# Sampling.net
KiCad netlist of a schematic drawn in Altium Designer
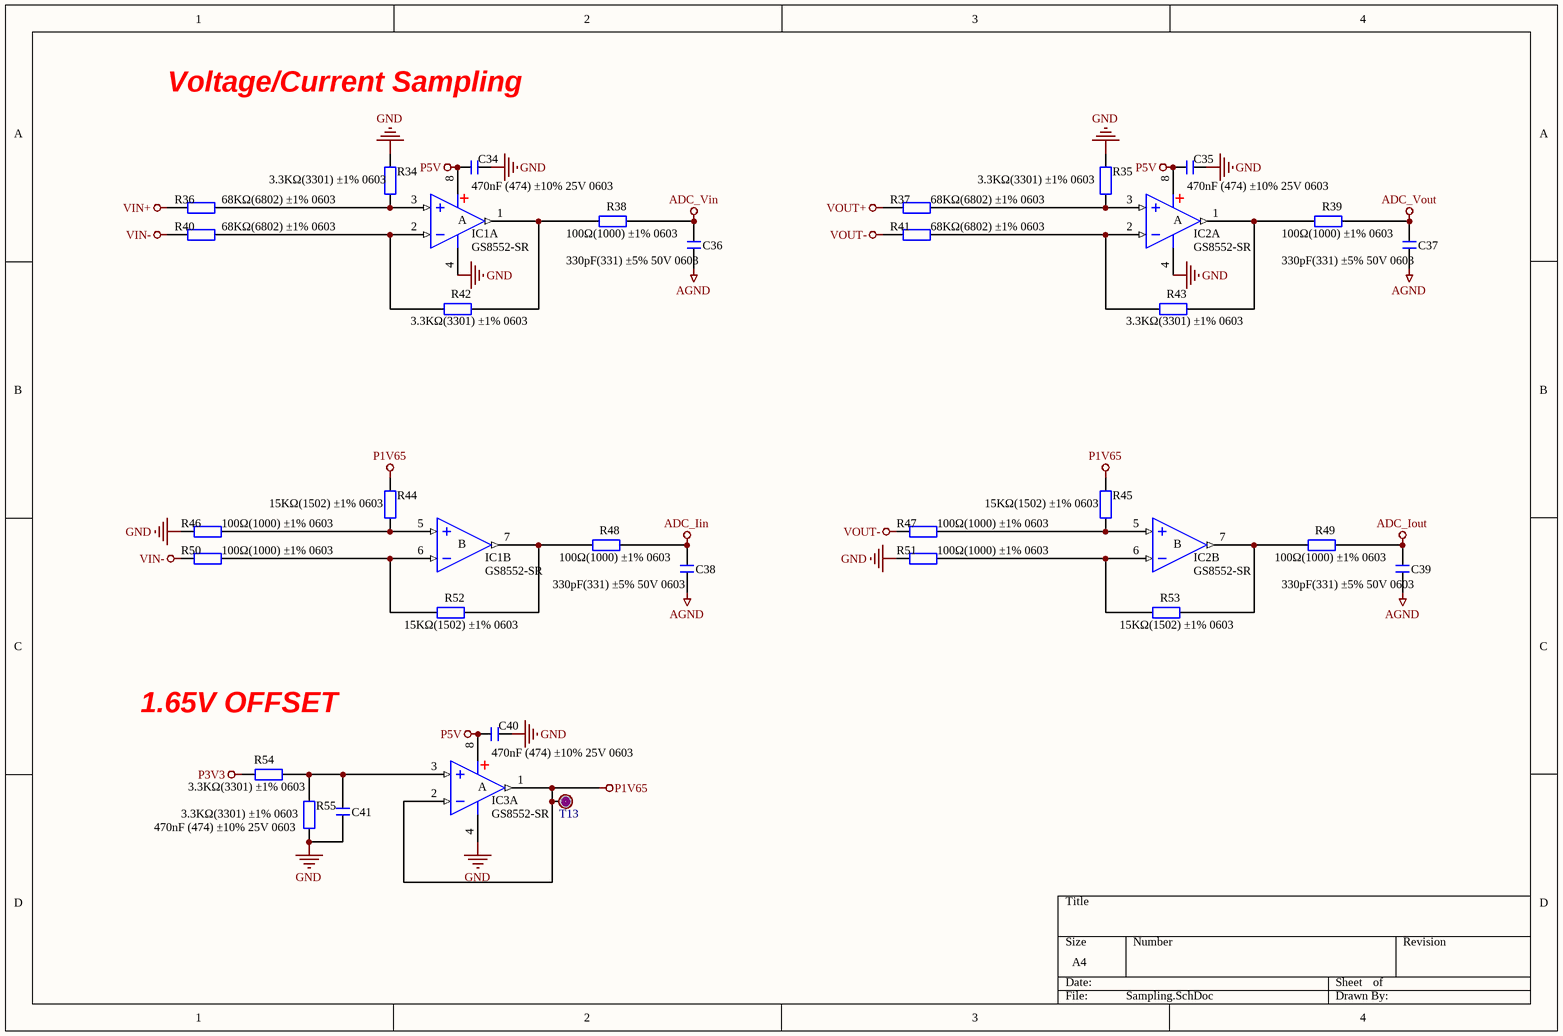
[diagram p0: Sampling.SchDoc]

(export (version "E")
  (design (tool "Eeschema 10.0.6"))
  (components
    (comp (ref "C34")
      (value "470nF (474) ±10% 25V 0603")
      (footprint "C 0603_L")
      (description "贴片电容")
      (libsource (lib "0.1 - 电阻-电容-电感") (part "C"))
    )
    (comp (ref "C35")
      (value "470nF (474) ±10% 25V 0603")
      (footprint "C 0603_L")
      (description "贴片电容")
      (libsource (lib "0.1 - 电阻-电容-电感") (part "C"))
    )
    (comp (ref "C36")
      (value "330pF(331) ±5% 50V 0603")
      (footprint "C 0603_L")
      (description "贴片电容")
      (libsource (lib "0.1 - 电阻-电容-电感") (part "C"))
    )
    (comp (ref "C37")
      (value "330pF(331) ±5% 50V 0603")
      (footprint "C 0603_L")
      (description "贴片电容")
      (libsource (lib "0.1 - 电阻-电容-电感") (part "C"))
    )
    (comp (ref "C38")
      (value "330pF(331) ±5% 50V 0603")
      (footprint "C 0603_L")
      (description "贴片电容")
      (libsource (lib "0.1 - 电阻-电容-电感") (part "C"))
    )
    (comp (ref "C39")
      (value "330pF(331) ±5% 50V 0603")
      (footprint "C 0603_L")
      (description "贴片电容")
      (libsource (lib "0.1 - 电阻-电容-电感") (part "C"))
    )
    (comp (ref "C40")
      (value "470nF (474) ±10% 25V 0603")
      (footprint "C 0603_L")
      (description "贴片电容")
      (libsource (lib "0.1 - 电阻-电容-电感") (part "C"))
    )
    (comp (ref "C41")
      (value "470nF (474) ±10% 25V 0603")
      (footprint "C 0603_L")
      (description "贴片电容")
      (libsource (lib "0.1 - 电阻-电容-电感") (part "C"))
    )
    (comp (ref "IC1")
      (value "GS8552-SR")
      (footprint "SOP8_N")
      (description "双路运放")
      (fields (field (name "版权归属") "源创客"))
      (libsource (lib "1.0 - 常见芯片") (part "LM358"))
    )
    (comp (ref "IC2")
      (value "GS8552-SR")
      (footprint "SOP8_N")
      (description "双路运放")
      (fields (field (name "版权归属") "源创客"))
      (libsource (lib "1.0 - 常见芯片") (part "LM358"))
    )
    (comp (ref "IC3")
      (value "GS8552-SR")
      (footprint "SOP8_N")
      (description "双路运放")
      (fields (field (name "版权归属") "源创客"))
      (libsource (lib "1.0 - 常见芯片") (part "LM358"))
    )
    (comp (ref "R34")
      (value "3.3KΩ(3301) ±1% 0603")
      (footprint "R 0603_L")
      (description "贴片电阻")
      (fields (field (name "版权归属") "来自淘宝 ID：黄晶宝石"))
      (libsource (lib "0.1 - 电阻-电容-电感") (part "R"))
    )
    (comp (ref "R35")
      (value "3.3KΩ(3301) ±1% 0603")
      (footprint "R 0603_L")
      (description "贴片电阻")
      (fields (field (name "版权归属") "来自淘宝 ID：黄晶宝石"))
      (libsource (lib "0.1 - 电阻-电容-电感") (part "R"))
    )
    (comp (ref "R36")
      (value "68KΩ(6802) ±1% 0603")
      (footprint "R 0603_L")
      (description "贴片电阻")
      (fields (field (name "版权归属") "来自淘宝 ID：黄晶宝石"))
      (libsource (lib "0.1 - 电阻-电容-电感") (part "R"))
    )
    (comp (ref "R37")
      (value "68KΩ(6802) ±1% 0603")
      (footprint "R 0603_L")
      (description "贴片电阻")
      (fields (field (name "版权归属") "来自淘宝 ID：黄晶宝石"))
      (libsource (lib "0.1 - 电阻-电容-电感") (part "R"))
    )
    (comp (ref "R38")
      (value "100Ω(1000) ±1% 0603")
      (footprint "R 0603_L")
      (description "贴片电阻")
      (fields (field (name "版权归属") "来自淘宝 ID：黄晶宝石"))
      (libsource (lib "0.1 - 电阻-电容-电感") (part "R"))
    )
    (comp (ref "R39")
      (value "100Ω(1000) ±1% 0603")
      (footprint "R 0603_L")
      (description "贴片电阻")
      (fields (field (name "版权归属") "来自淘宝 ID：黄晶宝石"))
      (libsource (lib "0.1 - 电阻-电容-电感") (part "R"))
    )
    (comp (ref "R40")
      (value "68KΩ(6802) ±1% 0603")
      (footprint "R 0603_L")
      (description "贴片电阻")
      (fields (field (name "版权归属") "来自淘宝 ID：黄晶宝石"))
      (libsource (lib "0.1 - 电阻-电容-电感") (part "R"))
    )
    (comp (ref "R41")
      (value "68KΩ(6802) ±1% 0603")
      (footprint "R 0603_L")
      (description "贴片电阻")
      (fields (field (name "版权归属") "来自淘宝 ID：黄晶宝石"))
      (libsource (lib "0.1 - 电阻-电容-电感") (part "R"))
    )
    (comp (ref "R42")
      (value "3.3KΩ(3301) ±1% 0603")
      (footprint "R 0603_L")
      (description "贴片电阻")
      (fields (field (name "版权归属") "来自淘宝 ID：黄晶宝石"))
      (libsource (lib "0.1 - 电阻-电容-电感") (part "R"))
    )
    (comp (ref "R43")
      (value "3.3KΩ(3301) ±1% 0603")
      (footprint "R 0603_L")
      (description "贴片电阻")
      (fields (field (name "版权归属") "来自淘宝 ID：黄晶宝石"))
      (libsource (lib "0.1 - 电阻-电容-电感") (part "R"))
    )
    (comp (ref "R44")
      (value "15KΩ(1502) ±1% 0603")
      (footprint "R 0603_L")
      (description "贴片电阻")
      (fields (field (name "版权归属") "来自淘宝 ID：黄晶宝石"))
      (libsource (lib "0.1 - 电阻-电容-电感") (part "R"))
    )
    (comp (ref "R45")
      (value "15KΩ(1502) ±1% 0603")
      (footprint "R 0603_L")
      (description "贴片电阻")
      (fields (field (name "版权归属") "来自淘宝 ID：黄晶宝石"))
      (libsource (lib "0.1 - 电阻-电容-电感") (part "R"))
    )
    (comp (ref "R46")
      (value "100Ω(1000) ±1% 0603")
      (footprint "R 0603_L")
      (description "贴片电阻")
      (fields (field (name "版权归属") "来自淘宝 ID：黄晶宝石"))
      (libsource (lib "0.1 - 电阻-电容-电感") (part "R"))
    )
    (comp (ref "R47")
      (value "100Ω(1000) ±1% 0603")
      (footprint "R 0603_L")
      (description "贴片电阻")
      (fields (field (name "版权归属") "来自淘宝 ID：黄晶宝石"))
      (libsource (lib "0.1 - 电阻-电容-电感") (part "R"))
    )
    (comp (ref "R48")
      (value "100Ω(1000) ±1% 0603")
      (footprint "R 0603_L")
      (description "贴片电阻")
      (fields (field (name "版权归属") "来自淘宝 ID：黄晶宝石"))
      (libsource (lib "0.1 - 电阻-电容-电感") (part "R"))
    )
    (comp (ref "R49")
      (value "100Ω(1000) ±1% 0603")
      (footprint "R 0603_L")
      (description "贴片电阻")
      (fields (field (name "版权归属") "来自淘宝 ID：黄晶宝石"))
      (libsource (lib "0.1 - 电阻-电容-电感") (part "R"))
    )
    (comp (ref "R50")
      (value "100Ω(1000) ±1% 0603")
      (footprint "R 0603_L")
      (description "贴片电阻")
      (fields (field (name "版权归属") "来自淘宝 ID：黄晶宝石"))
      (libsource (lib "0.1 - 电阻-电容-电感") (part "R"))
    )
    (comp (ref "R51")
      (value "100Ω(1000) ±1% 0603")
      (footprint "R 0603_L")
      (description "贴片电阻")
      (fields (field (name "版权归属") "来自淘宝 ID：黄晶宝石"))
      (libsource (lib "0.1 - 电阻-电容-电感") (part "R"))
    )
    (comp (ref "R52")
      (value "15KΩ(1502) ±1% 0603")
      (footprint "R 0603_L")
      (description "贴片电阻")
      (fields (field (name "版权归属") "来自淘宝 ID：黄晶宝石"))
      (libsource (lib "0.1 - 电阻-电容-电感") (part "R"))
    )
    (comp (ref "R53")
      (value "15KΩ(1502) ±1% 0603")
      (footprint "R 0603_L")
      (description "贴片电阻")
      (fields (field (name "版权归属") "来自淘宝 ID：黄晶宝石"))
      (libsource (lib "0.1 - 电阻-电容-电感") (part "R"))
    )
    (comp (ref "R54")
      (value "3.3KΩ(3301) ±1% 0603")
      (footprint "R 0603_L")
      (description "贴片电阻")
      (fields (field (name "版权归属") "来自淘宝 ID：黄晶宝石"))
      (libsource (lib "0.1 - 电阻-电容-电感") (part "R"))
    )
    (comp (ref "R55")
      (value "3.3KΩ(3301) ±1% 0603")
      (footprint "R 0603_L")
      (description "贴片电阻")
      (fields (field (name "版权归属") "来自淘宝 ID：黄晶宝石"))
      (libsource (lib "0.1 - 电阻-电容-电感") (part "R"))
    )
    (comp (ref "T13") (value "TestP") (footprint "TestP") (libsource (lib "CSS02404A") (part "TestP")))
  )
  (nets
    (net (code "1") (name "ADC_Iin") (class "Default")
      (node (ref "C38") (pin "2") (pinfunction "2_2") (pintype "passive"))
      (node (ref "R48") (pin "2") (pinfunction "2_2") (pintype "passive"))
    )
    (net (code "2") (name "ADC_Iout") (class "Default")
      (node (ref "C39") (pin "2") (pinfunction "2_2") (pintype "passive"))
      (node (ref "R49") (pin "2") (pinfunction "2_2") (pintype "passive"))
    )
    (net (code "3") (name "ADC_Vin") (class "Default")
      (node (ref "C36") (pin "2") (pinfunction "2_2") (pintype "passive"))
      (node (ref "R38") (pin "2") (pinfunction "2_2") (pintype "passive"))
    )
    (net (code "4") (name "ADC_Vout") (class "Default")
      (node (ref "C37") (pin "2") (pinfunction "2_2") (pintype "passive"))
      (node (ref "R39") (pin "2") (pinfunction "2_2") (pintype "passive"))
    )
    (net (code "5") (name "AGND") (class "Default")
      (node (ref "C36") (pin "1") (pinfunction "1_1") (pintype "passive"))
      (node (ref "C37") (pin "1") (pinfunction "1_1") (pintype "passive"))
      (node (ref "C38") (pin "1") (pinfunction "1_1") (pintype "passive"))
      (node (ref "C39") (pin "1") (pinfunction "1_1") (pintype "passive"))
    )
    (net (code "6") (name "GND") (class "Default")
      (node (ref "C34") (pin "1") (pinfunction "1_1") (pintype "passive"))
      (node (ref "C35") (pin "1") (pinfunction "1_1") (pintype "passive"))
      (node (ref "C40") (pin "1") (pinfunction "1_1") (pintype "passive"))
      (node (ref "C41") (pin "2") (pinfunction "2_2") (pintype "passive"))
      (node (ref "IC1") (pin "4") (pinfunction "V-_4") (pintype "power_in"))
      (node (ref "IC2") (pin "4") (pinfunction "V-_4") (pintype "power_in"))
      (node (ref "IC3") (pin "4") (pinfunction "V-_4") (pintype "power_in"))
      (node (ref "R34") (pin "2") (pinfunction "2_2") (pintype "passive"))
      (node (ref "R35") (pin "2") (pinfunction "2_2") (pintype "passive"))
      (node (ref "R46") (pin "1") (pinfunction "1_1") (pintype "passive"))
      (node (ref "R51") (pin "1") (pinfunction "1_1") (pintype "passive"))
      (node (ref "R55") (pin "2") (pinfunction "2_2") (pintype "passive"))
    )
    (net (code "7") (name "Net-(IC1A-IN+)") (class "Default")
      (node (ref "IC1") (pin "3") (pinfunction "IN+_3") (pintype "input"))
      (node (ref "R34") (pin "1") (pinfunction "1_1") (pintype "passive"))
      (node (ref "R36") (pin "2") (pinfunction "2_2") (pintype "passive"))
    )
    (net (code "8") (name "Net-(IC1A-IN-)") (class "Default")
      (node (ref "IC1") (pin "2") (pinfunction "IN-_2") (pintype "input"))
      (node (ref "R40") (pin "2") (pinfunction "2_2") (pintype "passive"))
      (node (ref "R42") (pin "1") (pinfunction "1_1") (pintype "passive"))
    )
    (net (code "9") (name "Net-(IC1A-OUT)") (class "Default")
      (node (ref "IC1") (pin "1") (pinfunction "OUT_1") (pintype "output"))
      (node (ref "R38") (pin "1") (pinfunction "1_1") (pintype "passive"))
      (node (ref "R42") (pin "2") (pinfunction "2_2") (pintype "passive"))
    )
    (net (code "10") (name "Net-(IC1B-IN+)") (class "Default")
      (node (ref "IC1") (pin "5") (pinfunction "IN+_5") (pintype "input"))
      (node (ref "R44") (pin "1") (pinfunction "1_1") (pintype "passive"))
      (node (ref "R46") (pin "2") (pinfunction "2_2") (pintype "passive"))
    )
    (net (code "11") (name "Net-(IC1B-IN-)") (class "Default")
      (node (ref "IC1") (pin "6") (pinfunction "IN-_6") (pintype "input"))
      (node (ref "R50") (pin "2") (pinfunction "2_2") (pintype "passive"))
      (node (ref "R52") (pin "1") (pinfunction "1_1") (pintype "passive"))
    )
    (net (code "12") (name "Net-(IC1B-OUT)") (class "Default")
      (node (ref "IC1") (pin "7") (pinfunction "OUT_7") (pintype "output"))
      (node (ref "R48") (pin "1") (pinfunction "1_1") (pintype "passive"))
      (node (ref "R52") (pin "2") (pinfunction "2_2") (pintype "passive"))
    )
    (net (code "13") (name "Net-(IC2A-IN+)") (class "Default")
      (node (ref "IC2") (pin "3") (pinfunction "IN+_3") (pintype "input"))
      (node (ref "R35") (pin "1") (pinfunction "1_1") (pintype "passive"))
      (node (ref "R37") (pin "2") (pinfunction "2_2") (pintype "passive"))
    )
    (net (code "14") (name "Net-(IC2A-IN-)") (class "Default")
      (node (ref "IC2") (pin "2") (pinfunction "IN-_2") (pintype "input"))
      (node (ref "R41") (pin "2") (pinfunction "2_2") (pintype "passive"))
      (node (ref "R43") (pin "1") (pinfunction "1_1") (pintype "passive"))
    )
    (net (code "15") (name "Net-(IC2A-OUT)") (class "Default")
      (node (ref "IC2") (pin "1") (pinfunction "OUT_1") (pintype "output"))
      (node (ref "R39") (pin "1") (pinfunction "1_1") (pintype "passive"))
      (node (ref "R43") (pin "2") (pinfunction "2_2") (pintype "passive"))
    )
    (net (code "16") (name "Net-(IC2B-IN+)") (class "Default")
      (node (ref "IC2") (pin "5") (pinfunction "IN+_5") (pintype "input"))
      (node (ref "R45") (pin "1") (pinfunction "1_1") (pintype "passive"))
      (node (ref "R47") (pin "2") (pinfunction "2_2") (pintype "passive"))
    )
    (net (code "17") (name "Net-(IC2B-IN-)") (class "Default")
      (node (ref "IC2") (pin "6") (pinfunction "IN-_6") (pintype "input"))
      (node (ref "R51") (pin "2") (pinfunction "2_2") (pintype "passive"))
      (node (ref "R53") (pin "1") (pinfunction "1_1") (pintype "passive"))
    )
    (net (code "18") (name "Net-(IC2B-OUT)") (class "Default")
      (node (ref "IC2") (pin "7") (pinfunction "OUT_7") (pintype "output"))
      (node (ref "R49") (pin "1") (pinfunction "1_1") (pintype "passive"))
      (node (ref "R53") (pin "2") (pinfunction "2_2") (pintype "passive"))
    )
    (net (code "19") (name "Net-(IC3A-IN+)") (class "Default")
      (node (ref "C41") (pin "1") (pinfunction "1_1") (pintype "passive"))
      (node (ref "IC3") (pin "3") (pinfunction "IN+_3") (pintype "input"))
      (node (ref "R54") (pin "1") (pinfunction "1_1") (pintype "passive"))
      (node (ref "R55") (pin "1") (pinfunction "1_1") (pintype "passive"))
    )
    (net (code "20") (name "P1V65") (class "Default")
      (node (ref "IC3") (pin "1") (pinfunction "OUT_1") (pintype "output"))
      (node (ref "IC3") (pin "2") (pinfunction "IN-_2") (pintype "input"))
      (node (ref "R44") (pin "2") (pinfunction "2_2") (pintype "passive"))
      (node (ref "R45") (pin "2") (pinfunction "2_2") (pintype "passive"))
      (node (ref "T13") (pin "0") (pinfunction "0_0") (pintype "passive"))
    )
    (net (code "21") (name "P3V3") (class "Default")
      (node (ref "R54") (pin "2") (pinfunction "2_2") (pintype "passive"))
    )
    (net (code "22") (name "P5V") (class "Default")
      (node (ref "C34") (pin "2") (pinfunction "2_2") (pintype "passive"))
      (node (ref "C35") (pin "2") (pinfunction "2_2") (pintype "passive"))
      (node (ref "C40") (pin "2") (pinfunction "2_2") (pintype "passive"))
      (node (ref "IC1") (pin "8") (pinfunction "V+_8") (pintype "power_in"))
      (node (ref "IC2") (pin "8") (pinfunction "V+_8") (pintype "power_in"))
      (node (ref "IC3") (pin "8") (pinfunction "V+_8") (pintype "power_in"))
    )
    (net (code "23") (name "VIN+") (class "Default")
      (node (ref "R36") (pin "1") (pinfunction "1_1") (pintype "passive"))
    )
    (net (code "24") (name "VIN-") (class "Default")
      (node (ref "R40") (pin "1") (pinfunction "1_1") (pintype "passive"))
      (node (ref "R50") (pin "1") (pinfunction "1_1") (pintype "passive"))
    )
    (net (code "25") (name "VOUT+") (class "Default")
      (node (ref "R37") (pin "1") (pinfunction "1_1") (pintype "passive"))
    )
    (net (code "26") (name "VOUT-") (class "Default")
      (node (ref "R41") (pin "1") (pinfunction "1_1") (pintype "passive"))
      (node (ref "R47") (pin "1") (pinfunction "1_1") (pintype "passive"))
    )
  )
)
